# smart_prototyping2.net
KiCad netlist of a schematic drawn in EAGLE
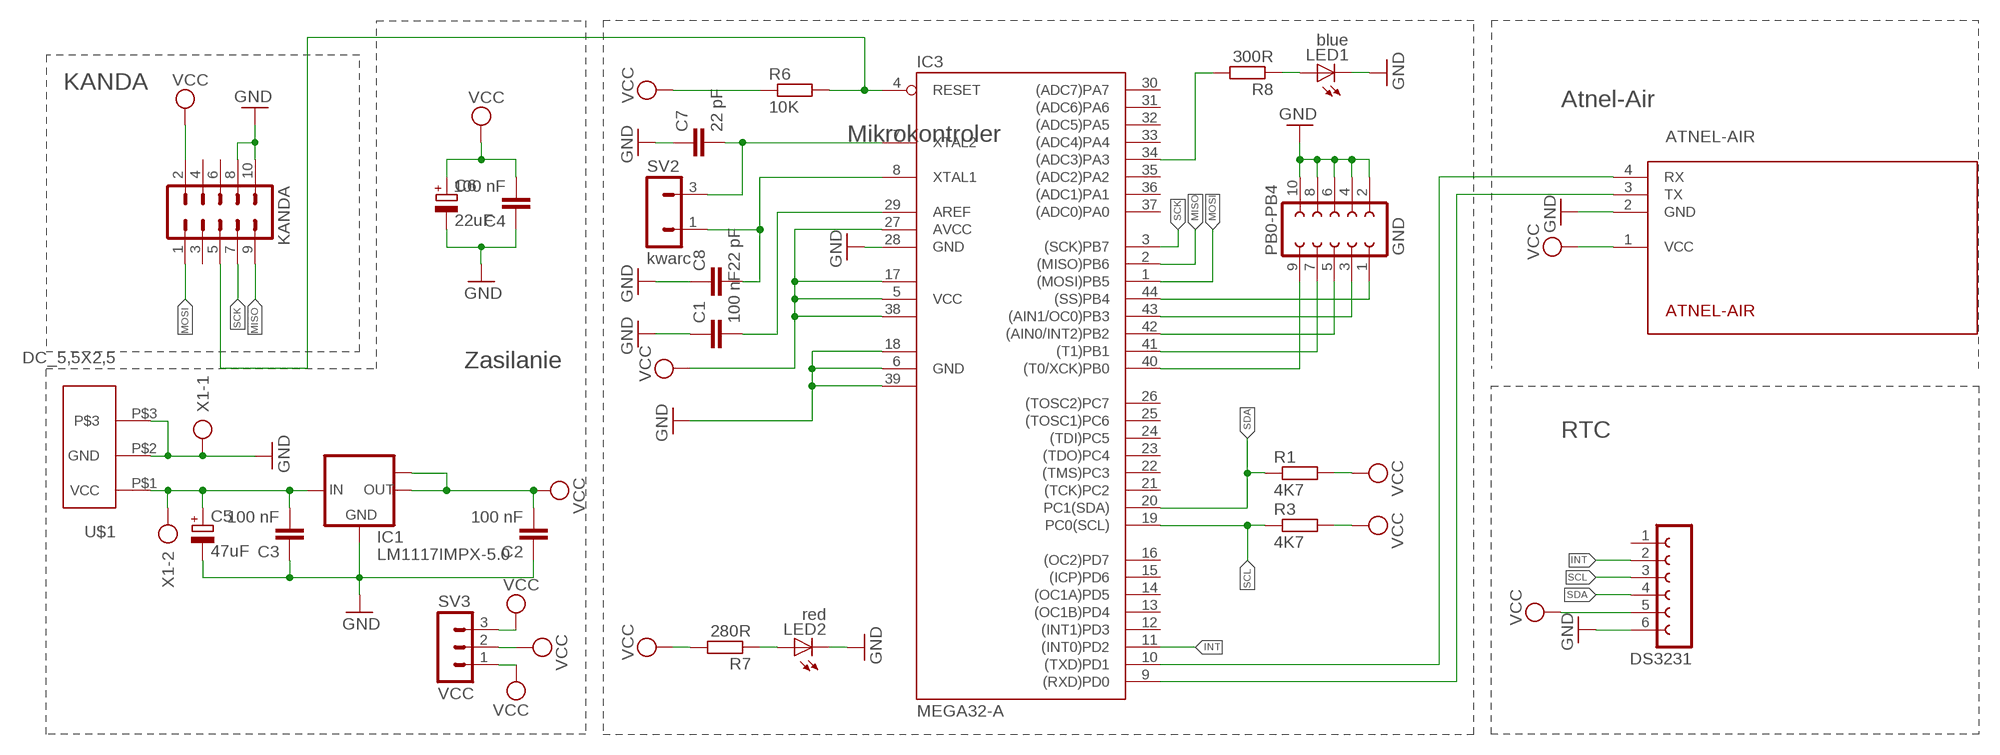
[diagram p0: schematic, sheet 1]

(export (version "E")
  (design (tool "Eeschema 10.0.6"))
  (components
    (comp (ref "ATNEL-AIR")
      (value "ATNEL-AIR")
      (footprint "eagle-import:ATNEL-AIR")
      (libsource (lib "eagle-import") (part "ATNEL-AIR"))
    )
    (comp (ref "C1")
      (value "100 nF")
      (footprint "eagle-import:C0805")
      (libsource (lib "eagle-import") (part "C-EUC0805"))
    )
    (comp (ref "C2")
      (value "100 nF")
      (footprint "eagle-import:C0805")
      (libsource (lib "eagle-import") (part "C-EUC0805"))
    )
    (comp (ref "C3")
      (value "100 nF")
      (footprint "eagle-import:C0805")
      (libsource (lib "eagle-import") (part "C-EUC0805"))
    )
    (comp (ref "C4")
      (value "100 nF")
      (footprint "eagle-import:C0805")
      (libsource (lib "eagle-import") (part "C-EUC0805"))
    )
    (comp (ref "C5")
      (value "47uF")
      (footprint "eagle-import:B45181A")
      (libsource (lib "eagle-import") (part "CPOL-EUB45181A"))
    )
    (comp (ref "C6")
      (value "22uF")
      (footprint "eagle-import:B45181A")
      (libsource (lib "eagle-import") (part "CPOL-EUB45181A"))
    )
    (comp (ref "C7")
      (value "22 pF")
      (footprint "eagle-import:C0805")
      (libsource (lib "eagle-import") (part "C-EUC0805"))
    )
    (comp (ref "C8")
      (value "22 pF")
      (footprint "eagle-import:C0805")
      (libsource (lib "eagle-import") (part "C-EUC0805"))
    )
    (comp (ref "DS3231")
      (value "FE06-1")
      (footprint "eagle-import:FE06")
      (libsource (lib "eagle-import") (part "FE06-1"))
    )
    (comp (ref "IC1")
      (value "LM1117IMPX-5.0")
      (footprint "eagle-import:SOT223")
      (libsource (lib "eagle-import") (part "LM1117IMPX-5.0"))
    )
    (comp (ref "IC3")
      (value "MEGA32-A")
      (footprint "eagle-import:TQFP44")
      (fields (field (name "MPN") "ATMEGA32-16AU"))
      (libsource (lib "eagle-import") (part "MEGA32-A"))
    )
    (comp (ref "KANDA")
      (value "ML10")
      (footprint "eagle-import:ML10")
      (libsource (lib "eagle-import") (part "ML10"))
    )
    (comp (ref "LED1")
      (value "blue")
      (footprint "eagle-import:CHIPLED_1206")
      (libsource (lib "eagle-import") (part "LEDCHIPLED_1206"))
    )
    (comp (ref "LED2")
      (value "red")
      (footprint "eagle-import:CHIPLED_1206")
      (libsource (lib "eagle-import") (part "LEDCHIPLED_1206"))
    )
    (comp (ref "PB0-PB4")
      (value "GND")
      (footprint "eagle-import:FE05-2")
      (libsource (lib "eagle-import") (part "FE05-2"))
    )
    (comp (ref "R1")
      (value "4K7")
      (footprint "eagle-import:R1206W")
      (libsource (lib "eagle-import") (part "R-EU_R1206W"))
    )
    (comp (ref "R3")
      (value "4K7")
      (footprint "eagle-import:R1206W")
      (libsource (lib "eagle-import") (part "R-EU_R1206W"))
    )
    (comp (ref "R6")
      (value "10K")
      (footprint "eagle-import:R1206W")
      (libsource (lib "eagle-import") (part "R-EU_R1206W"))
    )
    (comp (ref "R7")
      (value "280R")
      (footprint "eagle-import:R1206W")
      (libsource (lib "eagle-import") (part "R-EU_R1206W"))
    )
    (comp (ref "R8")
      (value "300R")
      (footprint "eagle-import:R1206W")
      (libsource (lib "eagle-import") (part "R-EU_R1206W"))
    )
    (comp (ref "SV2")
      (value "kwarc")
      (footprint "eagle-import:MA03-1")
      (libsource (lib "eagle-import") (part "con-lstb-wachcio_MA03-1"))
    )
    (comp (ref "SV3")
      (value "VCC")
      (footprint "eagle-import:MA03-1")
      (libsource (lib "eagle-import") (part "MA03-1"))
    )
    (comp (ref "U$1")
      (value "DC_5,5X2,5")
      (footprint "eagle-import:DC_5,5X2,5")
      (libsource (lib "eagle-import") (part "DC_5,5X2,5"))
    )
    (comp (ref "X1")
      (value "AK500/2")
      (footprint "eagle-import:AK500_2")
      (libsource (lib "eagle-import") (part "AK500/2"))
    )
  )
  (nets
    (net (code "1") (name "GND") (class "Default")
      (node (ref "ATNEL-AIR") (pin "2") (pinfunction "GND_2") (pintype "bidirectional"))
      (node (ref "C1") (pin "1") (pinfunction "1_1") (pintype "passive"))
      (node (ref "C2") (pin "1") (pinfunction "1_1") (pintype "passive"))
      (node (ref "C3") (pin "1") (pinfunction "1_1") (pintype "passive"))
      (node (ref "C4") (pin "1") (pinfunction "1_1") (pintype "passive"))
      (node (ref "C5") (pin "-") (pinfunction "-_-") (pintype "passive"))
      (node (ref "C6") (pin "-") (pinfunction "-_-") (pintype "passive"))
      (node (ref "C7") (pin "1") (pinfunction "1_1") (pintype "passive"))
      (node (ref "C8") (pin "1") (pinfunction "1_1") (pintype "passive"))
      (node (ref "DS3231") (pin "6") (pinfunction "6_6") (pintype "passive"))
      (node (ref "IC1") (pin "1") (pinfunction "GND_1") (pintype "input"))
      (node (ref "IC3") (pin "18") (pinfunction "GND1_18") (pintype "power_in"))
      (node (ref "IC3") (pin "28") (pinfunction "GND_28") (pintype "power_in"))
      (node (ref "IC3") (pin "39") (pinfunction "GND2_39") (pintype "power_in"))
      (node (ref "IC3") (pin "6") (pinfunction "GND_6") (pintype "power_in"))
      (node (ref "KANDA") (pin "10") (pinfunction "10_10") (pintype "passive"))
      (node (ref "KANDA") (pin "8") (pinfunction "8_8") (pintype "passive"))
      (node (ref "LED1") (pin "C") (pinfunction "C_C") (pintype "passive"))
      (node (ref "LED2") (pin "C") (pinfunction "C_C") (pintype "passive"))
      (node (ref "PB0-PB4") (pin "10") (pinfunction "10_10") (pintype "passive"))
      (node (ref "PB0-PB4") (pin "2") (pinfunction "2_2") (pintype "passive"))
      (node (ref "PB0-PB4") (pin "4") (pinfunction "4_4") (pintype "passive"))
      (node (ref "PB0-PB4") (pin "6") (pinfunction "6_6") (pintype "passive"))
      (node (ref "PB0-PB4") (pin "8") (pinfunction "8_8") (pintype "passive"))
      (node (ref "U$1") (pin "P$2") (pinfunction "GND_P$2") (pintype "bidirectional"))
      (node (ref "U$1") (pin "P$3") (pinfunction "P$3_P$3") (pintype "bidirectional"))
      (node (ref "X1") (pin "1") (pinfunction "KL_1") (pintype "passive"))
    )
    (net (code "2") (name "INT") (class "Default")
      (node (ref "DS3231") (pin "2") (pinfunction "2_2") (pintype "passive"))
      (node (ref "IC3") (pin "11") (pinfunction "(INT0)PD2_11") (pintype "bidirectional"))
    )
    (net (code "3") (name "MISO") (class "Default")
      (node (ref "IC3") (pin "2") (pinfunction "(MISO)PB6_2") (pintype "bidirectional"))
      (node (ref "KANDA") (pin "9") (pinfunction "9_9") (pintype "passive"))
    )
    (net (code "4") (name "MOSI") (class "Default")
      (node (ref "IC3") (pin "1") (pinfunction "(MOSI)PB5_1") (pintype "bidirectional"))
      (node (ref "KANDA") (pin "1") (pinfunction "1_1") (pintype "passive"))
    )
    (net (code "5") (name "Net-(ATNEL-AIR-RX)") (class "Default")
      (node (ref "ATNEL-AIR") (pin "4") (pinfunction "RX_4") (pintype "output"))
      (node (ref "IC3") (pin "10") (pinfunction "(TXD)PD1_10") (pintype "bidirectional"))
    )
    (net (code "6") (name "Net-(ATNEL-AIR-TX)") (class "Default")
      (node (ref "ATNEL-AIR") (pin "3") (pinfunction "TX_3") (pintype "input"))
      (node (ref "IC3") (pin "9") (pinfunction "(RXD)PD0_9") (pintype "bidirectional"))
    )
    (net (code "7") (name "Net-(IC1-IN)") (class "Default")
      (node (ref "C3") (pin "2") (pinfunction "2_2") (pintype "passive"))
      (node (ref "C5") (pin "+") (pinfunction "+_+") (pintype "passive"))
      (node (ref "IC1") (pin "3") (pinfunction "IN_3") (pintype "input"))
      (node (ref "U$1") (pin "P$1") (pinfunction "VCC_P$1") (pintype "bidirectional"))
      (node (ref "X1") (pin "2") (pinfunction "KL_2") (pintype "passive"))
    )
    (net (code "8") (name "Net-(IC3-(ADC3)PA3)") (class "Default")
      (node (ref "IC3") (pin "34") (pinfunction "(ADC3)PA3_34") (pintype "bidirectional"))
      (node (ref "R8") (pin "2") (pinfunction "2_2") (pintype "passive"))
    )
    (net (code "9") (name "Net-(IC3-(AIN0{slash}INT2)PB2)") (class "Default")
      (node (ref "IC3") (pin "42") (pinfunction "(AIN0/INT2)PB2_42") (pintype "bidirectional"))
      (node (ref "PB0-PB4") (pin "5") (pinfunction "5_5") (pintype "passive"))
    )
    (net (code "10") (name "Net-(IC3-(AIN1{slash}OC0)PB3)") (class "Default")
      (node (ref "IC3") (pin "43") (pinfunction "(AIN1/OC0)PB3_43") (pintype "bidirectional"))
      (node (ref "PB0-PB4") (pin "3") (pinfunction "3_3") (pintype "passive"))
    )
    (net (code "11") (name "Net-(IC3-(SS)PB4)") (class "Default")
      (node (ref "IC3") (pin "44") (pinfunction "(SS)PB4_44") (pintype "bidirectional"))
      (node (ref "PB0-PB4") (pin "1") (pinfunction "1_1") (pintype "passive"))
    )
    (net (code "12") (name "Net-(IC3-(T0{slash}XCK)PB0)") (class "Default")
      (node (ref "IC3") (pin "40") (pinfunction "(T0/XCK)PB0_40") (pintype "bidirectional"))
      (node (ref "PB0-PB4") (pin "9") (pinfunction "9_9") (pintype "passive"))
    )
    (net (code "13") (name "Net-(IC3-(T1)PB1)") (class "Default")
      (node (ref "IC3") (pin "41") (pinfunction "(T1)PB1_41") (pintype "bidirectional"))
      (node (ref "PB0-PB4") (pin "7") (pinfunction "7_7") (pintype "passive"))
    )
    (net (code "14") (name "Net-(IC3-AREF)") (class "Default")
      (node (ref "C1") (pin "2") (pinfunction "2_2") (pintype "passive"))
      (node (ref "IC3") (pin "29") (pinfunction "AREF_29") (pintype "passive"))
    )
    (net (code "15") (name "Net-(IC3-RESET)") (class "Default")
      (node (ref "IC3") (pin "4") (pinfunction "RESET_4") (pintype "input"))
      (node (ref "KANDA") (pin "5") (pinfunction "5_5") (pintype "passive"))
      (node (ref "R6") (pin "2") (pinfunction "2_2") (pintype "passive"))
    )
    (net (code "16") (name "Net-(IC3-XTAL1)") (class "Default")
      (node (ref "C8") (pin "2") (pinfunction "2_2") (pintype "passive"))
      (node (ref "IC3") (pin "8") (pinfunction "XTAL1_8") (pintype "bidirectional"))
      (node (ref "SV2") (pin "1") (pinfunction "1_1") (pintype "passive"))
    )
    (net (code "17") (name "Net-(IC3-XTAL2)") (class "Default")
      (node (ref "C7") (pin "2") (pinfunction "2_2") (pintype "passive"))
      (node (ref "IC3") (pin "7") (pinfunction "XTAL2_7") (pintype "bidirectional"))
      (node (ref "SV2") (pin "3") (pinfunction "3_3") (pintype "passive"))
    )
    (net (code "18") (name "Net-(LED1-PadA)") (class "Default")
      (node (ref "LED1") (pin "A") (pinfunction "A_A") (pintype "passive"))
      (node (ref "R8") (pin "1") (pinfunction "1_1") (pintype "passive"))
    )
    (net (code "19") (name "Net-(LED2-PadA)") (class "Default")
      (node (ref "LED2") (pin "A") (pinfunction "A_A") (pintype "passive"))
      (node (ref "R7") (pin "1") (pinfunction "1_1") (pintype "passive"))
    )
    (net (code "20") (name "SCK") (class "Default")
      (node (ref "IC3") (pin "3") (pinfunction "(SCK)PB7_3") (pintype "bidirectional"))
      (node (ref "KANDA") (pin "7") (pinfunction "7_7") (pintype "passive"))
    )
    (net (code "21") (name "SCL") (class "Default")
      (node (ref "DS3231") (pin "3") (pinfunction "3_3") (pintype "passive"))
      (node (ref "IC3") (pin "19") (pinfunction "PC0(SCL)_19") (pintype "bidirectional"))
      (node (ref "R3") (pin "1") (pinfunction "1_1") (pintype "passive"))
    )
    (net (code "22") (name "SDA") (class "Default")
      (node (ref "DS3231") (pin "4") (pinfunction "4_4") (pintype "passive"))
      (node (ref "IC3") (pin "20") (pinfunction "PC1(SDA)_20") (pintype "bidirectional"))
      (node (ref "R1") (pin "1") (pinfunction "1_1") (pintype "passive"))
    )
    (net (code "23") (name "VCC") (class "Default")
      (node (ref "ATNEL-AIR") (pin "1") (pinfunction "VCC_1") (pintype "bidirectional"))
      (node (ref "C2") (pin "2") (pinfunction "2_2") (pintype "passive"))
      (node (ref "C4") (pin "2") (pinfunction "2_2") (pintype "passive"))
      (node (ref "C6") (pin "+") (pinfunction "+_+") (pintype "passive"))
      (node (ref "DS3231") (pin "5") (pinfunction "5_5") (pintype "passive"))
      (node (ref "IC1") (pin "2") (pinfunction "OUT_2") (pintype "passive"))
      (node (ref "IC1") (pin "TAB") (pinfunction "OUT1_TAB") (pintype "passive"))
      (node (ref "IC3") (pin "17") (pinfunction "VCC1_17") (pintype "power_in"))
      (node (ref "IC3") (pin "27") (pinfunction "AVCC_27") (pintype "power_in"))
      (node (ref "IC3") (pin "38") (pinfunction "VCC2_38") (pintype "power_in"))
      (node (ref "IC3") (pin "5") (pinfunction "VCC_5") (pintype "power_in"))
      (node (ref "KANDA") (pin "2") (pinfunction "2_2") (pintype "passive"))
      (node (ref "R1") (pin "2") (pinfunction "2_2") (pintype "passive"))
      (node (ref "R3") (pin "2") (pinfunction "2_2") (pintype "passive"))
      (node (ref "R6") (pin "1") (pinfunction "1_1") (pintype "passive"))
      (node (ref "R7") (pin "2") (pinfunction "2_2") (pintype "passive"))
      (node (ref "SV3") (pin "1") (pinfunction "1_1") (pintype "passive"))
      (node (ref "SV3") (pin "2") (pinfunction "2_2") (pintype "passive"))
      (node (ref "SV3") (pin "3") (pinfunction "3_3") (pintype "passive"))
    )
    (net (code "24") (name "unconnected-(DS3231-Pad1)") (class "Default")
      (node (ref "DS3231") (pin "1") (pinfunction "1_1") (pintype "passive"))
    )
    (net (code "25") (name "unconnected-(IC3-(ADC0)PA0-Pad37)") (class "Default")
      (node (ref "IC3") (pin "37") (pinfunction "(ADC0)PA0_37") (pintype "bidirectional"))
    )
    (net (code "26") (name "unconnected-(IC3-(ADC1)PA1-Pad36)") (class "Default")
      (node (ref "IC3") (pin "36") (pinfunction "(ADC1)PA1_36") (pintype "bidirectional"))
    )
    (net (code "27") (name "unconnected-(IC3-(ADC2)PA2-Pad35)") (class "Default")
      (node (ref "IC3") (pin "35") (pinfunction "(ADC2)PA2_35") (pintype "bidirectional"))
    )
    (net (code "28") (name "unconnected-(IC3-(ADC4)PA4-Pad33)") (class "Default")
      (node (ref "IC3") (pin "33") (pinfunction "(ADC4)PA4_33") (pintype "bidirectional"))
    )
    (net (code "29") (name "unconnected-(IC3-(ADC5)PA5-Pad32)") (class "Default")
      (node (ref "IC3") (pin "32") (pinfunction "(ADC5)PA5_32") (pintype "bidirectional"))
    )
    (net (code "30") (name "unconnected-(IC3-(ADC6)PA6-Pad31)") (class "Default")
      (node (ref "IC3") (pin "31") (pinfunction "(ADC6)PA6_31") (pintype "bidirectional"))
    )
    (net (code "31") (name "unconnected-(IC3-(ADC7)PA7-Pad30)") (class "Default")
      (node (ref "IC3") (pin "30") (pinfunction "(ADC7)PA7_30") (pintype "bidirectional"))
    )
    (net (code "32") (name "unconnected-(IC3-(ICP)PD6-Pad15)") (class "Default")
      (node (ref "IC3") (pin "15") (pinfunction "(ICP)PD6_15") (pintype "bidirectional"))
    )
    (net (code "33") (name "unconnected-(IC3-(INT1)PD3-Pad12)") (class "Default")
      (node (ref "IC3") (pin "12") (pinfunction "(INT1)PD3_12") (pintype "bidirectional"))
    )
    (net (code "34") (name "unconnected-(IC3-(OC1A)PD5-Pad14)") (class "Default")
      (node (ref "IC3") (pin "14") (pinfunction "(OC1A)PD5_14") (pintype "bidirectional"))
    )
    (net (code "35") (name "unconnected-(IC3-(OC1B)PD4-Pad13)") (class "Default")
      (node (ref "IC3") (pin "13") (pinfunction "(OC1B)PD4_13") (pintype "bidirectional"))
    )
    (net (code "36") (name "unconnected-(IC3-(OC2)PD7-Pad16)") (class "Default")
      (node (ref "IC3") (pin "16") (pinfunction "(OC2)PD7_16") (pintype "bidirectional"))
    )
    (net (code "37") (name "unconnected-(IC3-(TCK)PC2-Pad21)") (class "Default")
      (node (ref "IC3") (pin "21") (pinfunction "(TCK)PC2_21") (pintype "bidirectional"))
    )
    (net (code "38") (name "unconnected-(IC3-(TDI)PC5-Pad24)") (class "Default")
      (node (ref "IC3") (pin "24") (pinfunction "(TDI)PC5_24") (pintype "bidirectional"))
    )
    (net (code "39") (name "unconnected-(IC3-(TDO)PC4-Pad23)") (class "Default")
      (node (ref "IC3") (pin "23") (pinfunction "(TDO)PC4_23") (pintype "bidirectional"))
    )
    (net (code "40") (name "unconnected-(IC3-(TMS)PC3-Pad22)") (class "Default")
      (node (ref "IC3") (pin "22") (pinfunction "(TMS)PC3_22") (pintype "bidirectional"))
    )
    (net (code "41") (name "unconnected-(IC3-(TOSC1)PC6-Pad25)") (class "Default")
      (node (ref "IC3") (pin "25") (pinfunction "(TOSC1)PC6_25") (pintype "bidirectional"))
    )
    (net (code "42") (name "unconnected-(IC3-(TOSC2)PC7-Pad26)") (class "Default")
      (node (ref "IC3") (pin "26") (pinfunction "(TOSC2)PC7_26") (pintype "bidirectional"))
    )
    (net (code "43") (name "unconnected-(KANDA-Pad3)") (class "Default")
      (node (ref "KANDA") (pin "3") (pinfunction "3_3") (pintype "passive"))
    )
    (net (code "44") (name "unconnected-(KANDA-Pad4)") (class "Default")
      (node (ref "KANDA") (pin "4") (pinfunction "4_4") (pintype "passive"))
    )
    (net (code "45") (name "unconnected-(KANDA-Pad6)") (class "Default")
      (node (ref "KANDA") (pin "6") (pinfunction "6_6") (pintype "passive"))
    )
  )
)
